# CAN_Shield_with_Regulator_v1_0.net
KiCad netlist of a schematic drawn in EAGLE
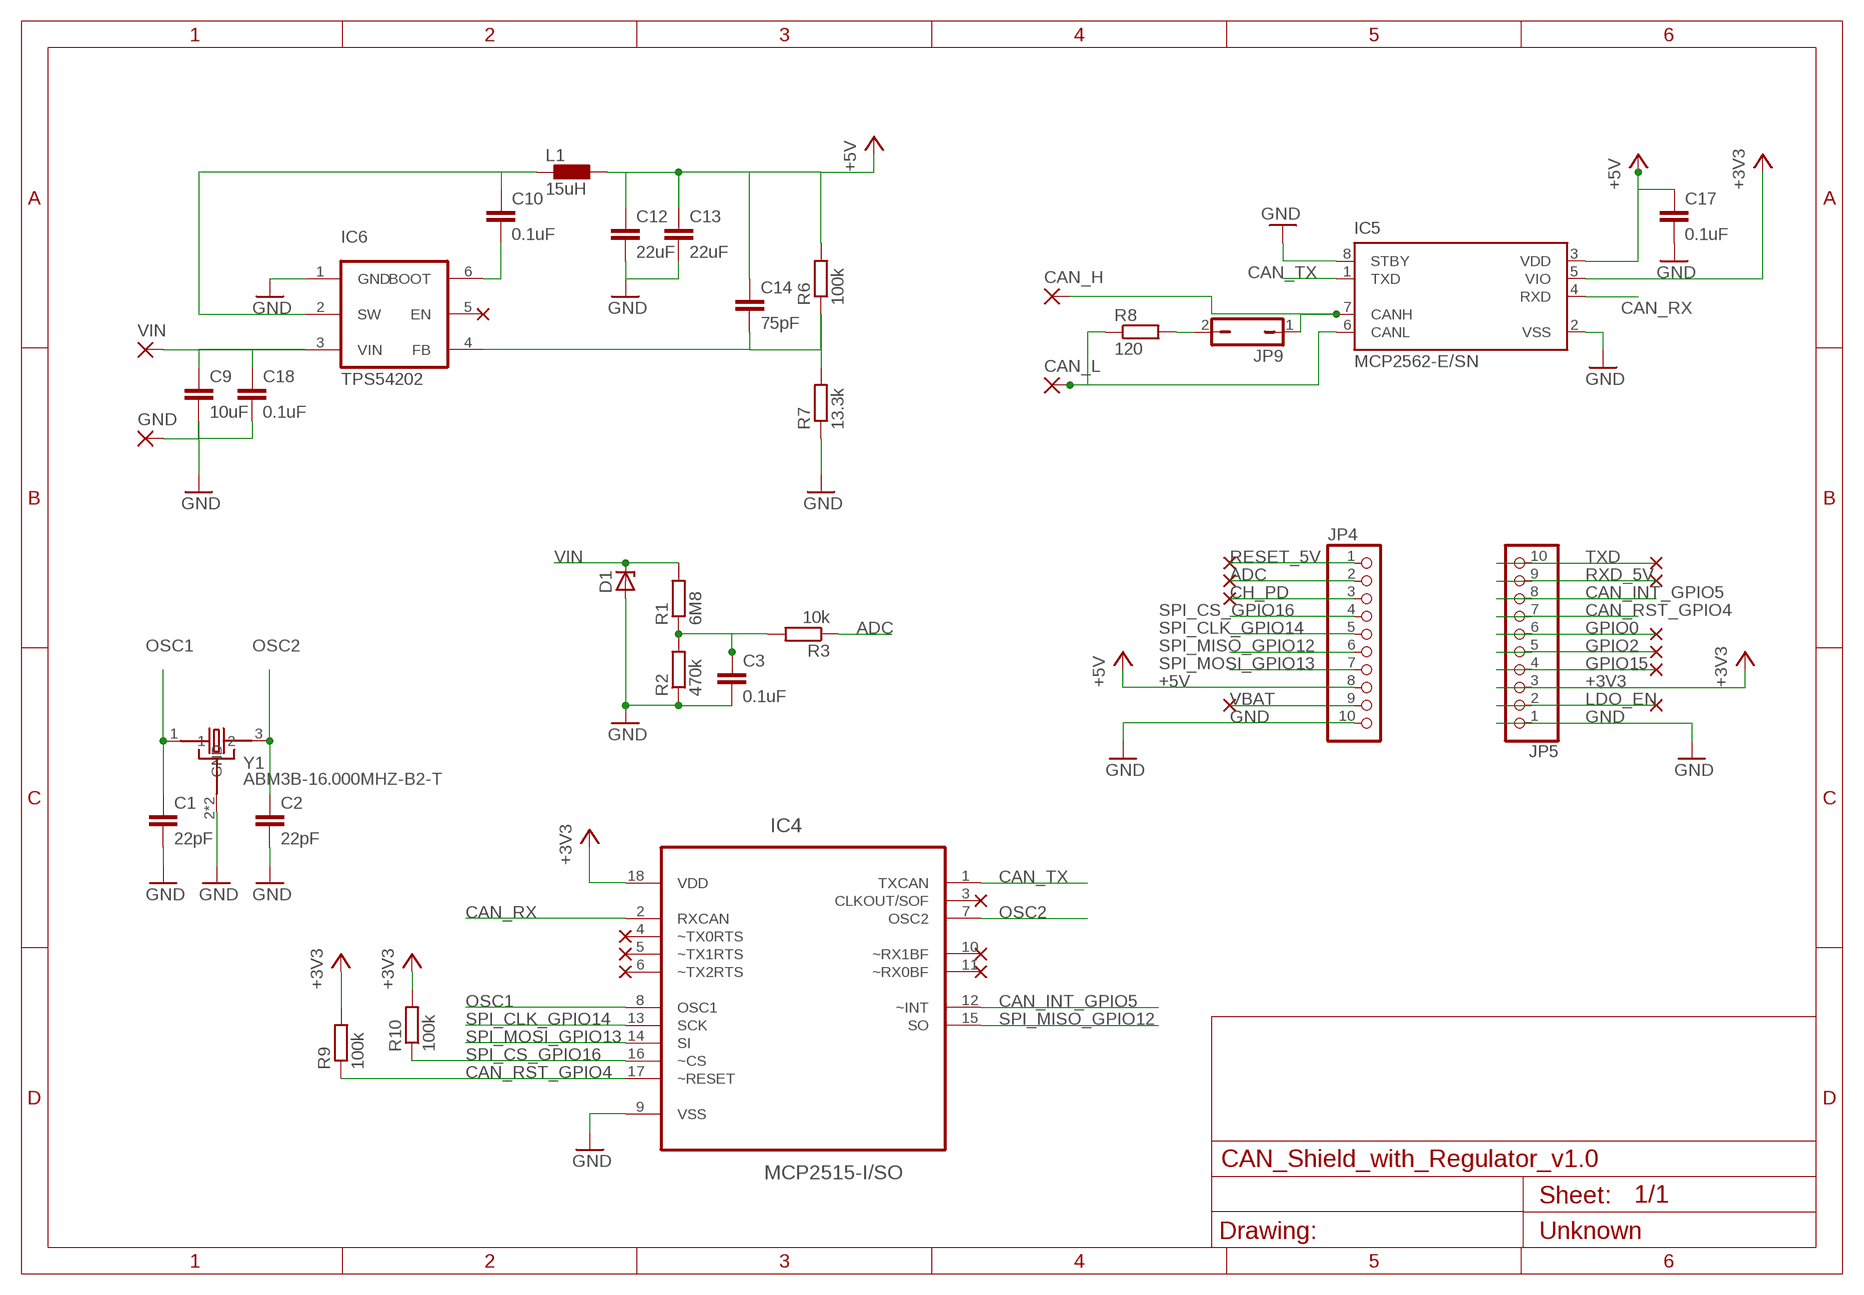
[diagram p0: schematic, sheet 1]

(export (version "E")
  (design (tool "Eeschema 10.0.6"))
  (components
    (comp (ref "C1")
      (value "22pF")
      (footprint "eagle-import:C0805")
      (libsource (lib "eagle-import") (part "C"))
    )
    (comp (ref "C2")
      (value "22pF")
      (footprint "eagle-import:C0805")
      (libsource (lib "eagle-import") (part "C"))
    )
    (comp (ref "C3")
      (value "0.1uF")
      (footprint "eagle-import:C1206")
      (libsource (lib "eagle-import") (part "CC1206"))
    )
    (comp (ref "C9")
      (value "10uF")
      (footprint "eagle-import:C1206")
      (libsource (lib "eagle-import") (part "CC1206"))
    )
    (comp (ref "C10")
      (value "0.1uF")
      (footprint "eagle-import:C1206")
      (libsource (lib "eagle-import") (part "CC1206"))
    )
    (comp (ref "C12")
      (value "22uF")
      (footprint "eagle-import:C1206")
      (libsource (lib "eagle-import") (part "CC1206"))
    )
    (comp (ref "C13")
      (value "22uF")
      (footprint "eagle-import:C1206")
      (libsource (lib "eagle-import") (part "CC1206"))
    )
    (comp (ref "C14")
      (value "75pF")
      (footprint "eagle-import:C1206")
      (libsource (lib "eagle-import") (part "CC1206"))
    )
    (comp (ref "C17")
      (value "0.1uF")
      (footprint "eagle-import:C1206")
      (libsource (lib "eagle-import") (part "CC1206"))
    )
    (comp (ref "C18")
      (value "0.1uF")
      (footprint "eagle-import:C1206")
      (libsource (lib "eagle-import") (part "CC1206"))
    )
    (comp (ref "CAN_H")
      (value "WIREPADSMD5-2,5")
      (footprint "eagle-import:5-2,5")
      (libsource (lib "eagle-import") (part "WIREPADSMD5-2,5"))
    )
    (comp (ref "CAN_L")
      (value "WIREPADSMD5-2,5")
      (footprint "eagle-import:5-2,5")
      (libsource (lib "eagle-import") (part "WIREPADSMD5-2,5"))
    )
    (comp (ref "D1")
      (value "ZENER-DIODE")
      (footprint "eagle-import:SOD3715X135N")
      (libsource (lib "eagle-import") (part "ZENER-DIODE"))
    )
    (comp (ref "GND")
      (value "WIREPADSMD5-2,5")
      (footprint "eagle-import:5-2,5")
      (libsource (lib "eagle-import") (part "WIREPADSMD5-2,5"))
    )
    (comp (ref "IC4")
      (value "MCP2515-I/SO")
      (footprint "eagle-import:SOIC127P1034X264-18N")
      (fields (field (name "MF") "Microchip"))
      (libsource (lib "eagle-import") (part "MCP2515-I/SO"))
    )
    (comp (ref "IC5")
      (value "MCP2562-E/SN")
      (footprint "eagle-import:SOIC127P600X175-8N")
      (fields (field (name "MF") "Microchip"))
      (libsource (lib "eagle-import") (part "MCP2562-E/SN"))
    )
    (comp (ref "IC6")
      (value "TPS54202")
      (footprint "eagle-import:SOT3-6P")
      (fields (field (name "MF") "Texas Instruments") (field (name "MP") "TPS54202DDCR"))
      (libsource (lib "eagle-import") (part "TPS54202"))
    )
    (comp (ref "JP4")
      (value "HEADER-1X1070MIL")
      (footprint "eagle-import:1X10_ROUND70")
      (libsource (lib "eagle-import") (part "HEADER-1X1070MIL"))
    )
    (comp (ref "JP5")
      (value "HEADER-1X1070MIL")
      (footprint "eagle-import:1X10_ROUND70")
      (libsource (lib "eagle-import") (part "HEADER-1X1070MIL"))
    )
    (comp (ref "JP9")
      (value "JP1Q")
      (footprint "eagle-import:JP1")
      (libsource (lib "eagle-import") (part "JP1Q"))
    )
    (comp (ref "L1")
      (value "15uH")
      (footprint "eagle-import:ER1515AH")
      (libsource (lib "eagle-import") (part "INDUCTOR"))
    )
    (comp (ref "R1")
      (value "6M8")
      (footprint "eagle-import:R1206")
      (libsource (lib "eagle-import") (part "RR1206"))
    )
    (comp (ref "R2")
      (value "470k")
      (footprint "eagle-import:R1206")
      (libsource (lib "eagle-import") (part "RR1206"))
    )
    (comp (ref "R3")
      (value "10k")
      (footprint "eagle-import:R1206")
      (libsource (lib "eagle-import") (part "RR1206"))
    )
    (comp (ref "R6")
      (value "100k")
      (footprint "eagle-import:R1206")
      (libsource (lib "eagle-import") (part "RR1206"))
    )
    (comp (ref "R7")
      (value "13.3k")
      (footprint "eagle-import:R1206")
      (libsource (lib "eagle-import") (part "RR1206"))
    )
    (comp (ref "R8")
      (value "120")
      (footprint "eagle-import:R1206")
      (libsource (lib "eagle-import") (part "RR1206"))
    )
    (comp (ref "R9")
      (value "100k")
      (footprint "eagle-import:R1206")
      (libsource (lib "eagle-import") (part "RR1206"))
    )
    (comp (ref "R10")
      (value "100k")
      (footprint "eagle-import:R1206")
      (libsource (lib "eagle-import") (part "RR1206"))
    )
    (comp (ref "VIN")
      (value "WIREPADSMD5-2,5")
      (footprint "eagle-import:5-2,5")
      (libsource (lib "eagle-import") (part "WIREPADSMD5-2,5"))
    )
    (comp (ref "Y1")
      (value "ABM3B-16.000MHZ-B2-T")
      (footprint "eagle-import:OSCSC500X320X110-4N")
      (fields (field (name "MF") "Abracon"))
      (libsource (lib "eagle-import") (part "ABM3B-16.000MHZ-B2-T"))
    )
  )
  (nets
    (net (code "1") (name "+3V3") (class "Default")
      (node (ref "IC4") (pin "18") (pinfunction "VDD_18") (pintype "power_in"))
      (node (ref "IC5") (pin "5") (pinfunction "VIO_5") (pintype "power_in"))
      (node (ref "JP5") (pin "3") (pinfunction "3_3") (pintype "passive"))
      (node (ref "R10") (pin "2") (pinfunction "2_2") (pintype "passive"))
      (node (ref "R9") (pin "2") (pinfunction "2_2") (pintype "passive"))
    )
    (net (code "2") (name "+5V") (class "Default")
      (node (ref "C12") (pin "1") (pinfunction "1_1") (pintype "passive"))
      (node (ref "C13") (pin "1") (pinfunction "1_1") (pintype "passive"))
      (node (ref "C14") (pin "1") (pinfunction "1_1") (pintype "passive"))
      (node (ref "C17") (pin "1") (pinfunction "1_1") (pintype "passive"))
      (node (ref "IC5") (pin "3") (pinfunction "VDD_3") (pintype "power_in"))
      (node (ref "JP4") (pin "8") (pinfunction "8_8") (pintype "passive"))
      (node (ref "L1") (pin "P$1") (pinfunction "1_P$1") (pintype "passive"))
      (node (ref "R6") (pin "2") (pinfunction "2_2") (pintype "passive"))
    )
    (net (code "3") (name "/ADC") (class "Default")
      (node (ref "JP4") (pin "2") (pinfunction "2_2") (pintype "passive"))
      (node (ref "R3") (pin "1") (pinfunction "1_1") (pintype "passive"))
    )
    (net (code "4") (name "/CAN_INT_GPIO5") (class "Default")
      (node (ref "IC4") (pin "12") (pinfunction "~{INT}_12") (pintype "output"))
      (node (ref "JP5") (pin "8") (pinfunction "8_8") (pintype "passive"))
    )
    (net (code "5") (name "/CAN_RST_GPIO4") (class "Default")
      (node (ref "IC4") (pin "17") (pinfunction "~{RESET}_17") (pintype "input"))
      (node (ref "JP5") (pin "7") (pinfunction "7_7") (pintype "passive"))
      (node (ref "R9") (pin "1") (pinfunction "1_1") (pintype "passive"))
    )
    (net (code "6") (name "/CAN_RX") (class "Default")
      (node (ref "IC4") (pin "2") (pinfunction "RXCAN_2") (pintype "input"))
      (node (ref "IC5") (pin "4") (pinfunction "RXD_4") (pintype "output"))
    )
    (net (code "7") (name "/CAN_TX") (class "Default")
      (node (ref "IC4") (pin "1") (pinfunction "TXCAN_1") (pintype "output"))
      (node (ref "IC5") (pin "1") (pinfunction "TXD_1") (pintype "input"))
    )
    (net (code "8") (name "/CH_PD") (class "Default")
      (node (ref "JP4") (pin "3") (pinfunction "3_3") (pintype "passive"))
    )
    (net (code "9") (name "/GPIO0") (class "Default")
      (node (ref "JP5") (pin "6") (pinfunction "6_6") (pintype "passive"))
    )
    (net (code "10") (name "/GPIO2") (class "Default")
      (node (ref "JP5") (pin "5") (pinfunction "5_5") (pintype "passive"))
    )
    (net (code "11") (name "/GPIO15") (class "Default")
      (node (ref "JP5") (pin "4") (pinfunction "4_4") (pintype "passive"))
    )
    (net (code "12") (name "/LDO_EN") (class "Default")
      (node (ref "JP5") (pin "2") (pinfunction "2_2") (pintype "passive"))
    )
    (net (code "13") (name "/OSC1") (class "Default")
      (node (ref "C1") (pin "1") (pinfunction "1_1") (pintype "passive"))
      (node (ref "IC4") (pin "8") (pinfunction "OSC1_8") (pintype "input"))
      (node (ref "Y1") (pin "1") (pinfunction "1_1") (pintype "passive"))
    )
    (net (code "14") (name "/OSC2") (class "Default")
      (node (ref "C2") (pin "1") (pinfunction "1_1") (pintype "passive"))
      (node (ref "IC4") (pin "7") (pinfunction "OSC2_7") (pintype "output"))
      (node (ref "Y1") (pin "3") (pinfunction "2_3") (pintype "passive"))
    )
    (net (code "15") (name "/RESET_5V") (class "Default")
      (node (ref "JP4") (pin "1") (pinfunction "1_1") (pintype "passive"))
    )
    (net (code "16") (name "/RXD_5V") (class "Default")
      (node (ref "JP5") (pin "9") (pinfunction "9_9") (pintype "passive"))
    )
    (net (code "17") (name "/SPI_CLK_GPIO14") (class "Default")
      (node (ref "IC4") (pin "13") (pinfunction "SCK_13") (pintype "input"))
      (node (ref "JP4") (pin "5") (pinfunction "5_5") (pintype "passive"))
    )
    (net (code "18") (name "/SPI_CS_GPIO16") (class "Default")
      (node (ref "IC4") (pin "16") (pinfunction "~{CS}_16") (pintype "input"))
      (node (ref "JP4") (pin "4") (pinfunction "4_4") (pintype "passive"))
      (node (ref "R10") (pin "1") (pinfunction "1_1") (pintype "passive"))
    )
    (net (code "19") (name "/SPI_MISO_GPIO12") (class "Default")
      (node (ref "IC4") (pin "15") (pinfunction "SO_15") (pintype "output"))
      (node (ref "JP4") (pin "6") (pinfunction "6_6") (pintype "passive"))
    )
    (net (code "20") (name "/SPI_MOSI_GPIO13") (class "Default")
      (node (ref "IC4") (pin "14") (pinfunction "SI_14") (pintype "input"))
      (node (ref "JP4") (pin "7") (pinfunction "7_7") (pintype "passive"))
    )
    (net (code "21") (name "/TXD") (class "Default")
      (node (ref "JP5") (pin "10") (pinfunction "10_10") (pintype "passive"))
    )
    (net (code "22") (name "/VBAT") (class "Default")
      (node (ref "JP4") (pin "9") (pinfunction "9_9") (pintype "passive"))
    )
    (net (code "23") (name "/VIN") (class "Default")
      (node (ref "C18") (pin "1") (pinfunction "1_1") (pintype "passive"))
      (node (ref "C9") (pin "1") (pinfunction "1_1") (pintype "passive"))
      (node (ref "D1") (pin "C") (pinfunction "C_C") (pintype "passive"))
      (node (ref "IC6") (pin "3") (pinfunction "VIN_3") (pintype "bidirectional"))
      (node (ref "R1") (pin "2") (pinfunction "2_2") (pintype "passive"))
      (node (ref "VIN") (pin "1") (pinfunction "P_1") (pintype "passive"))
    )
    (net (code "24") (name "GND") (class "Default")
      (node (ref "C1") (pin "2") (pinfunction "2_2") (pintype "passive"))
      (node (ref "C12") (pin "2") (pinfunction "2_2") (pintype "passive"))
      (node (ref "C13") (pin "2") (pinfunction "2_2") (pintype "passive"))
      (node (ref "C17") (pin "2") (pinfunction "2_2") (pintype "passive"))
      (node (ref "C18") (pin "2") (pinfunction "2_2") (pintype "passive"))
      (node (ref "C2") (pin "2") (pinfunction "2_2") (pintype "passive"))
      (node (ref "C3") (pin "2") (pinfunction "2_2") (pintype "passive"))
      (node (ref "C9") (pin "2") (pinfunction "2_2") (pintype "passive"))
      (node (ref "D1") (pin "A") (pinfunction "A_A") (pintype "passive"))
      (node (ref "GND") (pin "1") (pinfunction "P_1") (pintype "passive"))
      (node (ref "IC4") (pin "9") (pinfunction "VSS_9") (pintype "power_in"))
      (node (ref "IC5") (pin "2") (pinfunction "VSS_2") (pintype "power_in"))
      (node (ref "IC5") (pin "8") (pinfunction "STBY_8") (pintype "input"))
      (node (ref "IC6") (pin "1") (pinfunction "GND_1") (pintype "bidirectional"))
      (node (ref "JP4") (pin "10") (pinfunction "10_10") (pintype "passive"))
      (node (ref "JP5") (pin "1") (pinfunction "1_1") (pintype "passive"))
      (node (ref "R2") (pin "1") (pinfunction "1_1") (pintype "passive"))
      (node (ref "R7") (pin "1") (pinfunction "1_1") (pintype "passive"))
      (node (ref "Y1") (pin "2") (pinfunction "GND_2") (pintype "passive"))
      (node (ref "Y1") (pin "4") (pinfunction "GND_4") (pintype "passive"))
    )
    (net (code "25") (name "Net-(C3-Pad1)") (class "Default")
      (node (ref "C3") (pin "1") (pinfunction "1_1") (pintype "passive"))
      (node (ref "R1") (pin "1") (pinfunction "1_1") (pintype "passive"))
      (node (ref "R2") (pin "2") (pinfunction "2_2") (pintype "passive"))
      (node (ref "R3") (pin "2") (pinfunction "2_2") (pintype "passive"))
    )
    (net (code "26") (name "Net-(CAN_H-P)") (class "Default")
      (node (ref "CAN_H") (pin "1") (pinfunction "P_1") (pintype "passive"))
      (node (ref "IC5") (pin "7") (pinfunction "CANH_7") (pintype "input"))
      (node (ref "JP9") (pin "1") (pinfunction "1_1") (pintype "passive"))
    )
    (net (code "27") (name "Net-(CAN_L-P)") (class "Default")
      (node (ref "CAN_L") (pin "1") (pinfunction "P_1") (pintype "passive"))
      (node (ref "IC5") (pin "6") (pinfunction "CANL_6") (pintype "input"))
      (node (ref "R8") (pin "1") (pinfunction "1_1") (pintype "passive"))
    )
    (net (code "28") (name "Net-(IC6-BOOT)") (class "Default")
      (node (ref "C10") (pin "2") (pinfunction "2_2") (pintype "passive"))
      (node (ref "IC6") (pin "6") (pinfunction "BOOT_6") (pintype "bidirectional"))
    )
    (net (code "29") (name "Net-(IC6-FB)") (class "Default")
      (node (ref "C14") (pin "2") (pinfunction "2_2") (pintype "passive"))
      (node (ref "IC6") (pin "4") (pinfunction "FB_4") (pintype "bidirectional"))
      (node (ref "R6") (pin "1") (pinfunction "1_1") (pintype "passive"))
      (node (ref "R7") (pin "2") (pinfunction "2_2") (pintype "passive"))
    )
    (net (code "30") (name "Net-(IC6-SW)") (class "Default")
      (node (ref "C10") (pin "1") (pinfunction "1_1") (pintype "passive"))
      (node (ref "IC6") (pin "2") (pinfunction "SW_2") (pintype "bidirectional"))
      (node (ref "L1") (pin "P$2") (pinfunction "2_P$2") (pintype "passive"))
    )
    (net (code "31") (name "Net-(JP9-Pad2)") (class "Default")
      (node (ref "JP9") (pin "2") (pinfunction "2_2") (pintype "passive"))
      (node (ref "R8") (pin "2") (pinfunction "2_2") (pintype "passive"))
    )
    (net (code "32") (name "unconnected-(IC4-CLKOUT{slash}SOF-Pad3)") (class "Default")
      (node (ref "IC4") (pin "3") (pinfunction "CLKOUT/SOF_3") (pintype "output"))
    )
    (net (code "33") (name "unconnected-(IC4-~{RX0BF}-Pad11)") (class "Default")
      (node (ref "IC4") (pin "11") (pinfunction "~{RX0BF}_11") (pintype "output"))
    )
    (net (code "34") (name "unconnected-(IC4-~{RX1BF}-Pad10)") (class "Default")
      (node (ref "IC4") (pin "10") (pinfunction "~{RX1BF}_10") (pintype "output"))
    )
    (net (code "35") (name "unconnected-(IC4-~{TX0RTS}-Pad4)") (class "Default")
      (node (ref "IC4") (pin "4") (pinfunction "~{TX0RTS}_4") (pintype "input"))
    )
    (net (code "36") (name "unconnected-(IC4-~{TX1RTS}-Pad5)") (class "Default")
      (node (ref "IC4") (pin "5") (pinfunction "~{TX1RTS}_5") (pintype "input"))
    )
    (net (code "37") (name "unconnected-(IC4-~{TX2RTS}-Pad6)") (class "Default")
      (node (ref "IC4") (pin "6") (pinfunction "~{TX2RTS}_6") (pintype "input"))
    )
    (net (code "38") (name "unconnected-(IC6-EN-Pad5)") (class "Default")
      (node (ref "IC6") (pin "5") (pinfunction "EN_5") (pintype "bidirectional"))
    )
  )
)
